# USB.net
KiCad netlist of a schematic drawn in Altium Designer
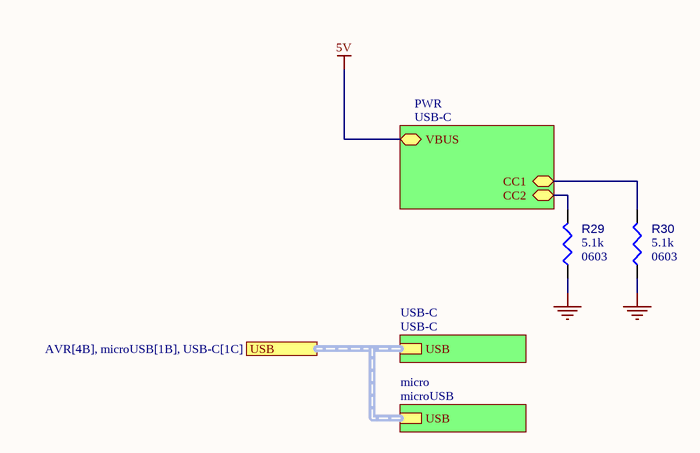
[diagram p0: USB.SchDoc]

(export (version "E")
  (design (tool "Eeschema 10.0.6"))
  (components
    (comp (ref "R29")
      (value "5.1k")
      (footprint "RESC1608X55X25ML10T15")
      (description "Chip Resistor, 1 KOhm, +/-1%, 0.1 W, -55 to 155 degC, 0603 (1608 Metric)")
      (fields
        (field (name "CASE/PACKAGE") "0603")
        (field (name "POWER") "100mW")
        (field (name "TOLERANCE") "1%")
      )
      (libsource (lib "Twill Technology Inc") (part "RES-2"))
    )
    (comp (ref "R30")
      (value "5.1k")
      (footprint "RESC1608X55X25ML10T15")
      (description "Chip Resistor, 1 KOhm, +/-1%, 0.1 W, -55 to 155 degC, 0603 (1608 Metric)")
      (fields
        (field (name "CASE/PACKAGE") "0603")
        (field (name "POWER") "100mW")
        (field (name "TOLERANCE") "1%")
      )
      (libsource (lib "Twill Technology Inc") (part "RES-2"))
    )
  )
  (nets
    (net (code "2") (name "/CC1") (class "Default")
      (node (ref "R30") (pin "2") (pinfunction "2_2") (pintype "passive"))
    )
    (net (code "3") (name "/CC2") (class "Default")
      (node (ref "R29") (pin "2") (pinfunction "2_2") (pintype "passive"))
    )
    (net (code "6") (name "GND") (class "Default")
      (node (ref "R29") (pin "1") (pinfunction "1_1") (pintype "passive"))
      (node (ref "R30") (pin "1") (pinfunction "1_1") (pintype "passive"))
    )
  )
)
